# rev1.net
KiCad netlist of a schematic drawn in EAGLE
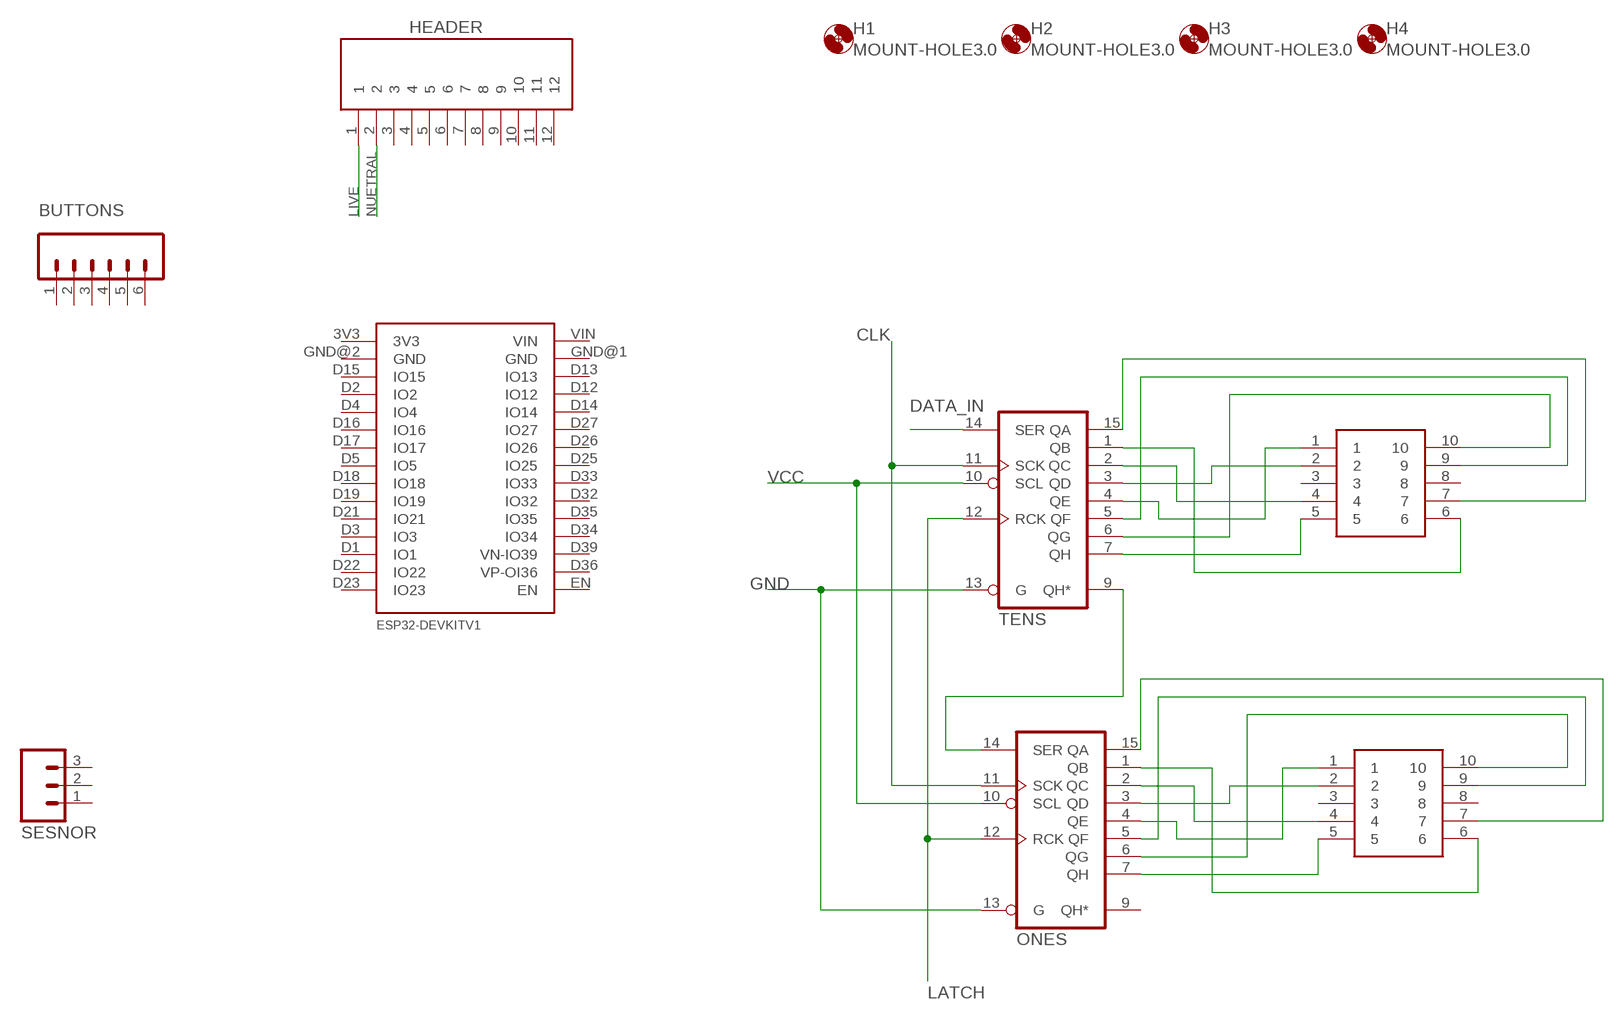
[diagram p0: schematic, sheet 1]

(export (version "E")
  (design (tool "Eeschema 10.0.6"))
  (components
    (comp (ref "BUTTONHEADER")
      (value "CONN_06LONGPADS")
      (footprint "eagle-import:1X06_LONGPADS")
      (libsource (lib "eagle-import") (part "CONN_06LONGPADS"))
    )
    (comp (ref "H1")
      (value "MOUNT-HOLE3.0")
      (footprint "eagle-import:3,0")
      (libsource (lib "eagle-import") (part "MOUNT-HOLE3.0"))
    )
    (comp (ref "H2")
      (value "MOUNT-HOLE3.0")
      (footprint "eagle-import:3,0")
      (libsource (lib "eagle-import") (part "MOUNT-HOLE3.0"))
    )
    (comp (ref "H3")
      (value "MOUNT-HOLE3.0")
      (footprint "eagle-import:3,0")
      (libsource (lib "eagle-import") (part "MOUNT-HOLE3.0"))
    )
    (comp (ref "H4")
      (value "MOUNT-HOLE3.0")
      (footprint "eagle-import:3,0")
      (libsource (lib "eagle-import") (part "MOUNT-HOLE3.0"))
    )
    (comp (ref "IC_ESP32")
      (value "ESP32DEVKITV1")
      (footprint "eagle-import:ESP32-DEVKITV1")
      (libsource (lib "eagle-import") (part "ESP32DEVKITV1"))
    )
    (comp (ref "MAINHEADER")
      (value "TB005-762-12BE")
      (footprint "eagle-import:CUI_TB005-762-12BE")
      (fields (field (name "MANUFACTURER") "CUI"))
      (libsource (lib "eagle-import") (part "TB005-762-12BE"))
    )
    (comp (ref "ONES_7SEG")
      (value "SC10-21SRWA")
      (footprint "eagle-import:DIPS3040W50P254L2400H1050Q10N")
      (fields (field (name "MOUSER_PART_NUMBER") "604-SC10-21SRWA"))
      (libsource (lib "eagle-import") (part "SC10-21SRWA"))
    )
    (comp (ref "ONES_SHIFTREG")
      (value "74LS595N")
      (footprint "eagle-import:DIL16")
      (libsource (lib "eagle-import") (part "74595NLS"))
    )
    (comp (ref "SENSOR")
      (value "CONN_03LONGPADS")
      (footprint "eagle-import:1X03_LONGPADS")
      (libsource (lib "eagle-import") (part "CONN_03LONGPADS"))
    )
    (comp (ref "TENS_7SEG")
      (value "SC10-21SRWA")
      (footprint "eagle-import:DIPS3040W50P254L2400H1050Q10N")
      (fields (field (name "MOUSER_PART_NUMBER") "604-SC10-21SRWA"))
      (libsource (lib "eagle-import") (part "SC10-21SRWA"))
    )
    (comp (ref "TENS_SHIFTREG")
      (value "74LS595N")
      (footprint "eagle-import:DIL16")
      (libsource (lib "eagle-import") (part "74595NLS"))
    )
  )
  (nets
    (net (code "1") (name "/CLK") (class "Default")
      (node (ref "ONES_SHIFTREG") (pin "11") (pinfunction "SCK_11") (pintype "input"))
      (node (ref "TENS_SHIFTREG") (pin "11") (pinfunction "SCK_11") (pintype "input"))
    )
    (net (code "2") (name "/DATA_IN") (class "Default")
      (node (ref "TENS_SHIFTREG") (pin "14") (pinfunction "SER_14") (pintype "input"))
    )
    (net (code "3") (name "/GND") (class "Default")
      (node (ref "ONES_SHIFTREG") (pin "13") (pinfunction "G_13") (pintype "input"))
      (node (ref "TENS_SHIFTREG") (pin "13") (pinfunction "G_13") (pintype "input"))
    )
    (net (code "4") (name "/LATCH") (class "Default")
      (node (ref "ONES_SHIFTREG") (pin "12") (pinfunction "RCK_12") (pintype "input"))
      (node (ref "TENS_SHIFTREG") (pin "12") (pinfunction "RCK_12") (pintype "input"))
    )
    (net (code "5") (name "/LIVE") (class "Default")
      (node (ref "MAINHEADER") (pin "1") (pinfunction "1_1") (pintype "passive"))
    )
    (net (code "6") (name "/NUETRAL") (class "Default")
      (node (ref "MAINHEADER") (pin "2") (pinfunction "2_2") (pintype "passive"))
    )
    (net (code "7") (name "/VCC") (class "Default")
      (node (ref "ONES_SHIFTREG") (pin "10") (pinfunction "SCL_10") (pintype "input"))
      (node (ref "TENS_SHIFTREG") (pin "10") (pinfunction "SCL_10") (pintype "input"))
    )
    (net (code "8") (name "Net-(ONES_SHIFTREGA-QA)") (class "Default")
      (node (ref "ONES_7SEG") (pin "7") (pinfunction "7_7") (pintype "bidirectional"))
      (node (ref "ONES_SHIFTREG") (pin "15") (pinfunction "QA_15") (pintype "tri_state"))
    )
    (net (code "9") (name "Net-(ONES_SHIFTREGA-QB)") (class "Default")
      (node (ref "ONES_7SEG") (pin "6") (pinfunction "6_6") (pintype "bidirectional"))
      (node (ref "ONES_SHIFTREG") (pin "1") (pinfunction "QB_1") (pintype "tri_state"))
    )
    (net (code "10") (name "Net-(ONES_SHIFTREGA-QC)") (class "Default")
      (node (ref "ONES_7SEG") (pin "4") (pinfunction "4_4") (pintype "bidirectional"))
      (node (ref "ONES_SHIFTREG") (pin "2") (pinfunction "QC_2") (pintype "tri_state"))
    )
    (net (code "11") (name "Net-(ONES_SHIFTREGA-QD)") (class "Default")
      (node (ref "ONES_7SEG") (pin "2") (pinfunction "2_2") (pintype "bidirectional"))
      (node (ref "ONES_SHIFTREG") (pin "3") (pinfunction "QD_3") (pintype "tri_state"))
    )
    (net (code "12") (name "Net-(ONES_SHIFTREGA-QE)") (class "Default")
      (node (ref "ONES_7SEG") (pin "1") (pinfunction "1_1") (pintype "bidirectional"))
      (node (ref "ONES_SHIFTREG") (pin "4") (pinfunction "QE_4") (pintype "tri_state"))
    )
    (net (code "13") (name "Net-(ONES_SHIFTREGA-QF)") (class "Default")
      (node (ref "ONES_7SEG") (pin "9") (pinfunction "9_9") (pintype "bidirectional"))
      (node (ref "ONES_SHIFTREG") (pin "5") (pinfunction "QF_5") (pintype "tri_state"))
    )
    (net (code "14") (name "Net-(ONES_SHIFTREGA-QG)") (class "Default")
      (node (ref "ONES_7SEG") (pin "10") (pinfunction "10_10") (pintype "bidirectional"))
      (node (ref "ONES_SHIFTREG") (pin "6") (pinfunction "QG_6") (pintype "tri_state"))
    )
    (net (code "15") (name "Net-(ONES_SHIFTREGA-QH)") (class "Default")
      (node (ref "ONES_7SEG") (pin "5") (pinfunction "5_5") (pintype "bidirectional"))
      (node (ref "ONES_SHIFTREG") (pin "7") (pinfunction "QH_7") (pintype "tri_state"))
    )
    (net (code "16") (name "Net-(ONES_SHIFTREGA-SER)") (class "Default")
      (node (ref "ONES_SHIFTREG") (pin "14") (pinfunction "SER_14") (pintype "input"))
      (node (ref "TENS_SHIFTREG") (pin "9") (pinfunction "QH*_9") (pintype "tri_state"))
    )
    (net (code "17") (name "Net-(TENS_SHIFTREGA-QA)") (class "Default")
      (node (ref "TENS_7SEG") (pin "7") (pinfunction "7_7") (pintype "bidirectional"))
      (node (ref "TENS_SHIFTREG") (pin "15") (pinfunction "QA_15") (pintype "tri_state"))
    )
    (net (code "18") (name "Net-(TENS_SHIFTREGA-QB)") (class "Default")
      (node (ref "TENS_7SEG") (pin "6") (pinfunction "6_6") (pintype "bidirectional"))
      (node (ref "TENS_SHIFTREG") (pin "1") (pinfunction "QB_1") (pintype "tri_state"))
    )
    (net (code "19") (name "Net-(TENS_SHIFTREGA-QC)") (class "Default")
      (node (ref "TENS_7SEG") (pin "4") (pinfunction "4_4") (pintype "bidirectional"))
      (node (ref "TENS_SHIFTREG") (pin "2") (pinfunction "QC_2") (pintype "tri_state"))
    )
    (net (code "20") (name "Net-(TENS_SHIFTREGA-QD)") (class "Default")
      (node (ref "TENS_7SEG") (pin "2") (pinfunction "2_2") (pintype "bidirectional"))
      (node (ref "TENS_SHIFTREG") (pin "3") (pinfunction "QD_3") (pintype "tri_state"))
    )
    (net (code "21") (name "Net-(TENS_SHIFTREGA-QE)") (class "Default")
      (node (ref "TENS_7SEG") (pin "1") (pinfunction "1_1") (pintype "bidirectional"))
      (node (ref "TENS_SHIFTREG") (pin "4") (pinfunction "QE_4") (pintype "tri_state"))
    )
    (net (code "22") (name "Net-(TENS_SHIFTREGA-QF)") (class "Default")
      (node (ref "TENS_7SEG") (pin "9") (pinfunction "9_9") (pintype "bidirectional"))
      (node (ref "TENS_SHIFTREG") (pin "5") (pinfunction "QF_5") (pintype "tri_state"))
    )
    (net (code "23") (name "Net-(TENS_SHIFTREGA-QG)") (class "Default")
      (node (ref "TENS_7SEG") (pin "10") (pinfunction "10_10") (pintype "bidirectional"))
      (node (ref "TENS_SHIFTREG") (pin "6") (pinfunction "QG_6") (pintype "tri_state"))
    )
    (net (code "24") (name "Net-(TENS_SHIFTREGA-QH)") (class "Default")
      (node (ref "TENS_7SEG") (pin "5") (pinfunction "5_5") (pintype "bidirectional"))
      (node (ref "TENS_SHIFTREG") (pin "7") (pinfunction "QH_7") (pintype "tri_state"))
    )
    (net (code "25") (name "unconnected-(BUTTONHEADER-Pad1)") (class "Default")
      (node (ref "BUTTONHEADER") (pin "1") (pinfunction "1_1") (pintype "passive"))
    )
    (net (code "26") (name "unconnected-(BUTTONHEADER-Pad2)") (class "Default")
      (node (ref "BUTTONHEADER") (pin "2") (pinfunction "2_2") (pintype "passive"))
    )
    (net (code "27") (name "unconnected-(BUTTONHEADER-Pad3)") (class "Default")
      (node (ref "BUTTONHEADER") (pin "3") (pinfunction "3_3") (pintype "passive"))
    )
    (net (code "28") (name "unconnected-(BUTTONHEADER-Pad4)") (class "Default")
      (node (ref "BUTTONHEADER") (pin "4") (pinfunction "4_4") (pintype "passive"))
    )
    (net (code "29") (name "unconnected-(BUTTONHEADER-Pad5)") (class "Default")
      (node (ref "BUTTONHEADER") (pin "5") (pinfunction "5_5") (pintype "passive"))
    )
    (net (code "30") (name "unconnected-(BUTTONHEADER-Pad6)") (class "Default")
      (node (ref "BUTTONHEADER") (pin "6") (pinfunction "6_6") (pintype "passive"))
    )
    (net (code "31") (name "unconnected-(IC_ESP32-GND-PadGND@1)") (class "Default")
      (node (ref "IC_ESP32") (pin "GND@1") (pinfunction "GND_GND@1") (pintype "bidirectional"))
    )
    (net (code "32") (name "unconnected-(IC_ESP32-GND-PadGND@2)") (class "Default")
      (node (ref "IC_ESP32") (pin "GND@2") (pinfunction "GND_GND@2") (pintype "bidirectional"))
    )
    (net (code "33") (name "unconnected-(IC_ESP32-IO1-PadD1)") (class "Default")
      (node (ref "IC_ESP32") (pin "D1") (pinfunction "IO1_D1") (pintype "bidirectional"))
    )
    (net (code "34") (name "unconnected-(IC_ESP32-IO2-PadD2)") (class "Default")
      (node (ref "IC_ESP32") (pin "D2") (pinfunction "IO2_D2") (pintype "bidirectional"))
    )
    (net (code "35") (name "unconnected-(IC_ESP32-IO3-PadD3)") (class "Default")
      (node (ref "IC_ESP32") (pin "D3") (pinfunction "IO3_D3") (pintype "bidirectional"))
    )
    (net (code "36") (name "unconnected-(IC_ESP32-IO4-PadD4)") (class "Default")
      (node (ref "IC_ESP32") (pin "D4") (pinfunction "IO4_D4") (pintype "bidirectional"))
    )
    (net (code "37") (name "unconnected-(IC_ESP32-IO5-PadD5)") (class "Default")
      (node (ref "IC_ESP32") (pin "D5") (pinfunction "IO5_D5") (pintype "bidirectional"))
    )
    (net (code "38") (name "unconnected-(IC_ESP32-IO12-PadD12)") (class "Default")
      (node (ref "IC_ESP32") (pin "D12") (pinfunction "IO12_D12") (pintype "bidirectional"))
    )
    (net (code "39") (name "unconnected-(IC_ESP32-IO13-PadD13)") (class "Default")
      (node (ref "IC_ESP32") (pin "D13") (pinfunction "IO13_D13") (pintype "bidirectional"))
    )
    (net (code "40") (name "unconnected-(IC_ESP32-IO14-PadD14)") (class "Default")
      (node (ref "IC_ESP32") (pin "D14") (pinfunction "IO14_D14") (pintype "bidirectional"))
    )
    (net (code "41") (name "unconnected-(IC_ESP32-IO15-PadD15)") (class "Default")
      (node (ref "IC_ESP32") (pin "D15") (pinfunction "IO15_D15") (pintype "bidirectional"))
    )
    (net (code "42") (name "unconnected-(IC_ESP32-IO16-PadD16)") (class "Default")
      (node (ref "IC_ESP32") (pin "D16") (pinfunction "IO16_D16") (pintype "bidirectional"))
    )
    (net (code "43") (name "unconnected-(IC_ESP32-IO17-PadD17)") (class "Default")
      (node (ref "IC_ESP32") (pin "D17") (pinfunction "IO17_D17") (pintype "bidirectional"))
    )
    (net (code "44") (name "unconnected-(IC_ESP32-IO18-PadD18)") (class "Default")
      (node (ref "IC_ESP32") (pin "D18") (pinfunction "IO18_D18") (pintype "bidirectional"))
    )
    (net (code "45") (name "unconnected-(IC_ESP32-IO19-PadD19)") (class "Default")
      (node (ref "IC_ESP32") (pin "D19") (pinfunction "IO19_D19") (pintype "bidirectional"))
    )
    (net (code "46") (name "unconnected-(IC_ESP32-IO21-PadD21)") (class "Default")
      (node (ref "IC_ESP32") (pin "D21") (pinfunction "IO21_D21") (pintype "bidirectional"))
    )
    (net (code "47") (name "unconnected-(IC_ESP32-IO22-PadD22)") (class "Default")
      (node (ref "IC_ESP32") (pin "D22") (pinfunction "IO22_D22") (pintype "bidirectional"))
    )
    (net (code "48") (name "unconnected-(IC_ESP32-IO23-PadD23)") (class "Default")
      (node (ref "IC_ESP32") (pin "D23") (pinfunction "IO23_D23") (pintype "bidirectional"))
    )
    (net (code "49") (name "unconnected-(IC_ESP32-IO25-PadD25)") (class "Default")
      (node (ref "IC_ESP32") (pin "D25") (pinfunction "IO25_D25") (pintype "bidirectional"))
    )
    (net (code "50") (name "unconnected-(IC_ESP32-IO26-PadD26)") (class "Default")
      (node (ref "IC_ESP32") (pin "D26") (pinfunction "IO26_D26") (pintype "bidirectional"))
    )
    (net (code "51") (name "unconnected-(IC_ESP32-IO27-PadD27)") (class "Default")
      (node (ref "IC_ESP32") (pin "D27") (pinfunction "IO27_D27") (pintype "bidirectional"))
    )
    (net (code "52") (name "unconnected-(IC_ESP32-IO32-PadD32)") (class "Default")
      (node (ref "IC_ESP32") (pin "D32") (pinfunction "IO32_D32") (pintype "bidirectional"))
    )
    (net (code "53") (name "unconnected-(IC_ESP32-IO33-PadD33)") (class "Default")
      (node (ref "IC_ESP32") (pin "D33") (pinfunction "IO33_D33") (pintype "bidirectional"))
    )
    (net (code "54") (name "unconnected-(IC_ESP32-IO34-PadD34)") (class "Default")
      (node (ref "IC_ESP32") (pin "D34") (pinfunction "IO34_D34") (pintype "bidirectional"))
    )
    (net (code "55") (name "unconnected-(IC_ESP32-IO35-PadD35)") (class "Default")
      (node (ref "IC_ESP32") (pin "D35") (pinfunction "IO35_D35") (pintype "bidirectional"))
    )
    (net (code "56") (name "unconnected-(IC_ESP32-Pad3V3)") (class "Default")
      (node (ref "IC_ESP32") (pin "3V3") (pinfunction "3V3_3V3") (pintype "bidirectional"))
    )
    (net (code "57") (name "unconnected-(IC_ESP32-PadEN)") (class "Default")
      (node (ref "IC_ESP32") (pin "EN") (pinfunction "EN_EN") (pintype "bidirectional"))
    )
    (net (code "58") (name "unconnected-(IC_ESP32-PadVIN)") (class "Default")
      (node (ref "IC_ESP32") (pin "VIN") (pinfunction "VIN_VIN") (pintype "bidirectional"))
    )
    (net (code "59") (name "unconnected-(IC_ESP32-VN-IO39-PadD39)") (class "Default")
      (node (ref "IC_ESP32") (pin "D39") (pinfunction "VN-IO39_D39") (pintype "bidirectional"))
    )
    (net (code "60") (name "unconnected-(IC_ESP32-VP-OI36-PadD36)") (class "Default")
      (node (ref "IC_ESP32") (pin "D36") (pinfunction "VP-OI36_D36") (pintype "bidirectional"))
    )
    (net (code "61") (name "unconnected-(MAINHEADER-Pad3)") (class "Default")
      (node (ref "MAINHEADER") (pin "3") (pinfunction "3_3") (pintype "passive"))
    )
    (net (code "62") (name "unconnected-(MAINHEADER-Pad4)") (class "Default")
      (node (ref "MAINHEADER") (pin "4") (pinfunction "4_4") (pintype "passive"))
    )
    (net (code "63") (name "unconnected-(MAINHEADER-Pad5)") (class "Default")
      (node (ref "MAINHEADER") (pin "5") (pinfunction "5_5") (pintype "passive"))
    )
    (net (code "64") (name "unconnected-(MAINHEADER-Pad6)") (class "Default")
      (node (ref "MAINHEADER") (pin "6") (pinfunction "6_6") (pintype "passive"))
    )
    (net (code "65") (name "unconnected-(MAINHEADER-Pad7)") (class "Default")
      (node (ref "MAINHEADER") (pin "7") (pinfunction "7_7") (pintype "passive"))
    )
    (net (code "66") (name "unconnected-(MAINHEADER-Pad8)") (class "Default")
      (node (ref "MAINHEADER") (pin "8") (pinfunction "8_8") (pintype "passive"))
    )
    (net (code "67") (name "unconnected-(MAINHEADER-Pad9)") (class "Default")
      (node (ref "MAINHEADER") (pin "9") (pinfunction "9_9") (pintype "passive"))
    )
    (net (code "68") (name "unconnected-(MAINHEADER-Pad10)") (class "Default")
      (node (ref "MAINHEADER") (pin "10") (pinfunction "10_10") (pintype "passive"))
    )
    (net (code "69") (name "unconnected-(MAINHEADER-Pad11)") (class "Default")
      (node (ref "MAINHEADER") (pin "11") (pinfunction "11_11") (pintype "passive"))
    )
    (net (code "70") (name "unconnected-(MAINHEADER-Pad12)") (class "Default")
      (node (ref "MAINHEADER") (pin "12") (pinfunction "12_12") (pintype "passive"))
    )
    (net (code "71") (name "unconnected-(ONES_7SEG-Pad3)") (class "Default")
      (node (ref "ONES_7SEG") (pin "3") (pinfunction "3_3") (pintype "bidirectional"))
    )
    (net (code "72") (name "unconnected-(ONES_7SEG-Pad8)") (class "Default")
      (node (ref "ONES_7SEG") (pin "8") (pinfunction "8_8") (pintype "bidirectional"))
    )
    (net (code "73") (name "unconnected-(ONES_SHIFTREGA-QH*-Pad9)") (class "Default")
      (node (ref "ONES_SHIFTREG") (pin "9") (pinfunction "QH*_9") (pintype "tri_state"))
    )
    (net (code "74") (name "unconnected-(SENSOR-Pad1)") (class "Default")
      (node (ref "SENSOR") (pin "1") (pinfunction "1_1") (pintype "passive"))
    )
    (net (code "75") (name "unconnected-(SENSOR-Pad2)") (class "Default")
      (node (ref "SENSOR") (pin "2") (pinfunction "2_2") (pintype "passive"))
    )
    (net (code "76") (name "unconnected-(SENSOR-Pad3)") (class "Default")
      (node (ref "SENSOR") (pin "3") (pinfunction "3_3") (pintype "passive"))
    )
    (net (code "77") (name "unconnected-(TENS_7SEG-Pad3)") (class "Default")
      (node (ref "TENS_7SEG") (pin "3") (pinfunction "3_3") (pintype "bidirectional"))
    )
    (net (code "78") (name "unconnected-(TENS_7SEG-Pad8)") (class "Default")
      (node (ref "TENS_7SEG") (pin "8") (pinfunction "8_8") (pintype "bidirectional"))
    )
  )
)
